# Mini_Black_Pill_grblHAL_v1.net
KiCad netlist of a schematic drawn in EAGLE
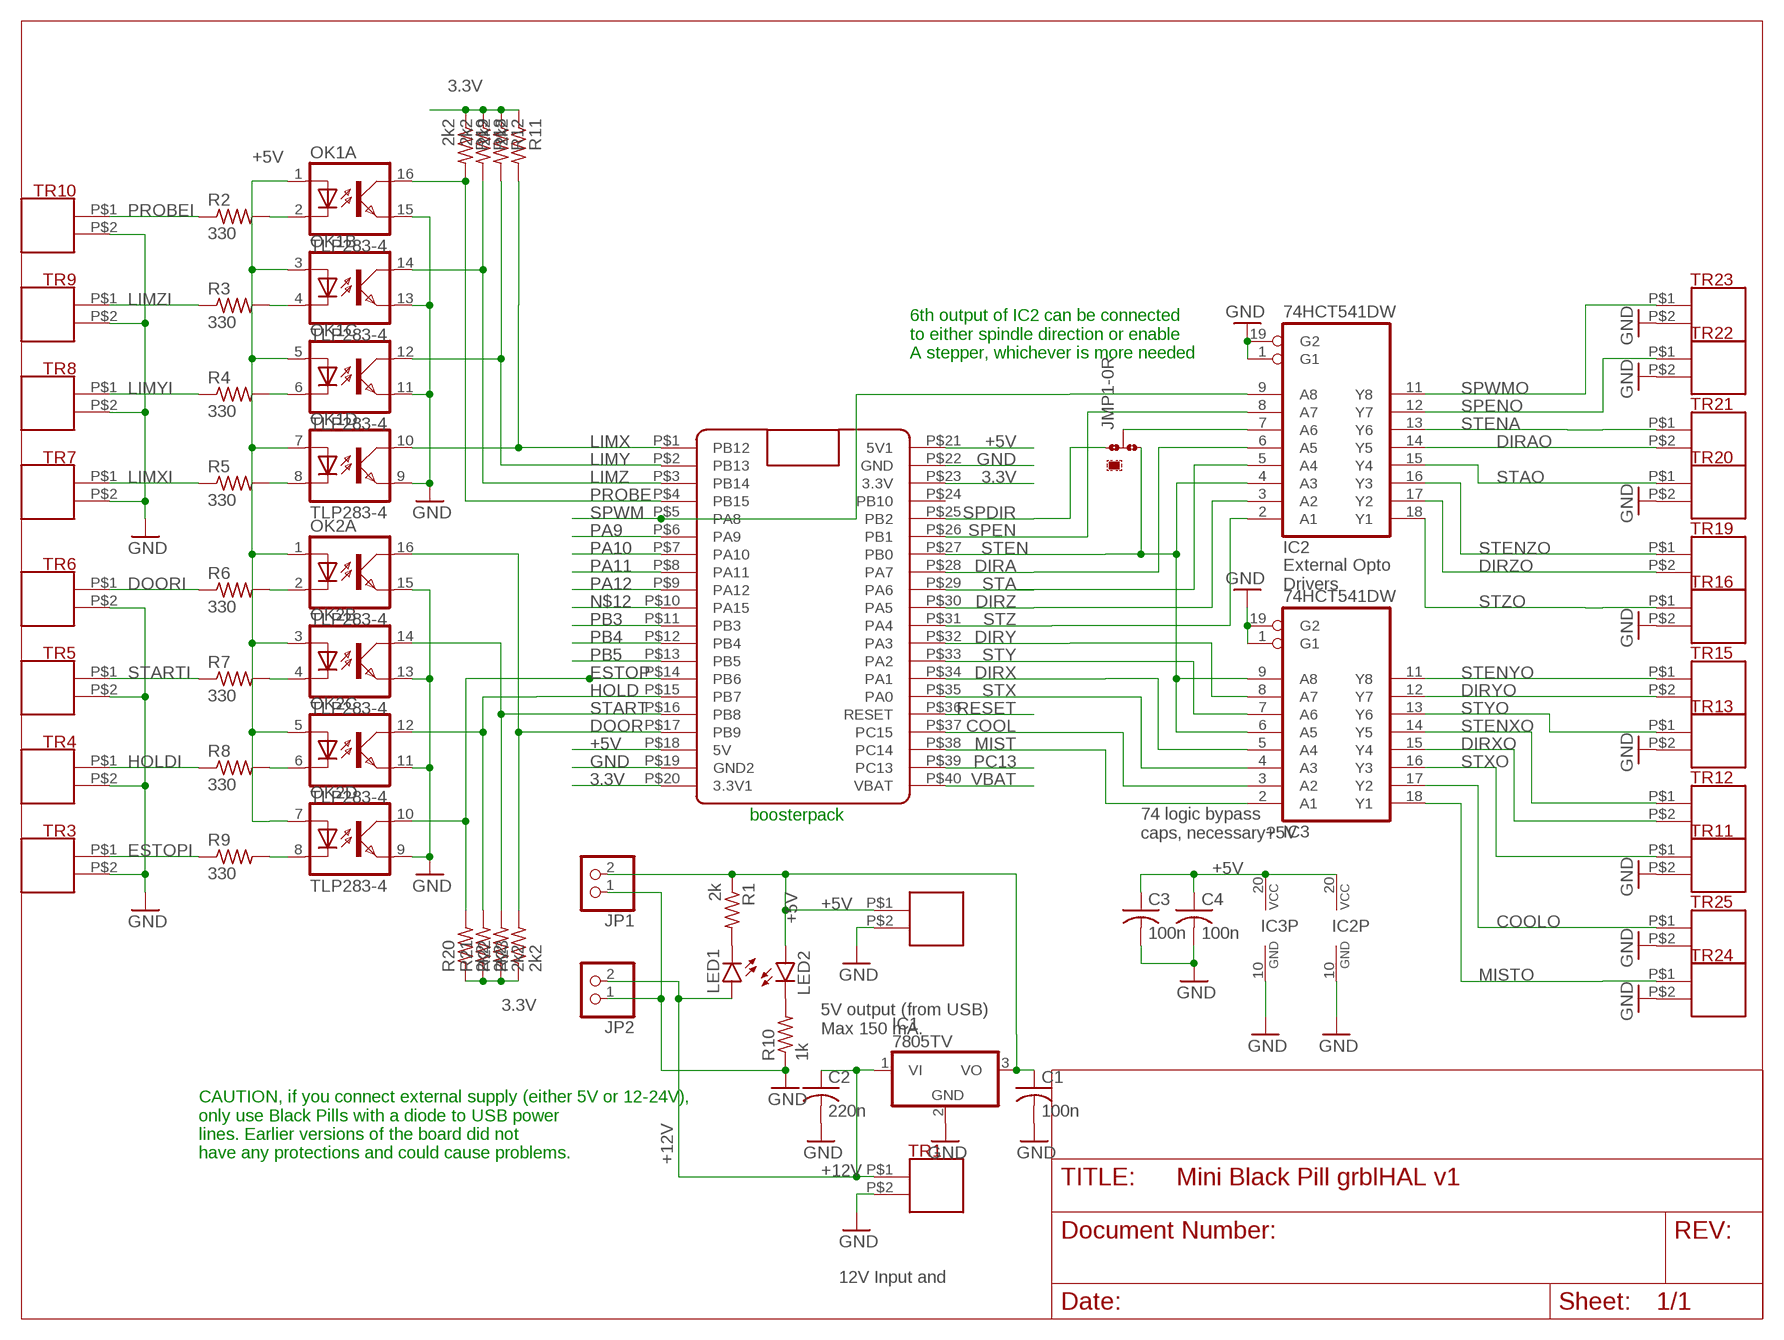
[diagram p0: schematic, sheet 1]

(export (version "E")
  (design (tool "Eeschema 10.0.6"))
  (components
    (comp (ref "C1")
      (value "100n")
      (footprint "eagle-import:C0805")
      (libsource (lib "eagle-import") (part "C-USC0805"))
    )
    (comp (ref "C2")
      (value "220n")
      (footprint "eagle-import:C0805")
      (libsource (lib "eagle-import") (part "C-USC0805"))
    )
    (comp (ref "C3")
      (value "100n")
      (footprint "eagle-import:C0805")
      (libsource (lib "eagle-import") (part "C-USC0805"))
    )
    (comp (ref "C4")
      (value "100n")
      (footprint "eagle-import:C0805")
      (libsource (lib "eagle-import") (part "C-USC0805"))
    )
    (comp (ref "IC1")
      (value "7805TV")
      (footprint "eagle-import:TO220V")
      (libsource (lib "eagle-import") (part "78TV05"))
    )
    (comp (ref "IC2")
      (value "74HCT541DW")
      (footprint "eagle-import:SO20W")
      (libsource (lib "eagle-import") (part "74541DWHCT"))
    )
    (comp (ref "IC3")
      (value "74HCT541DW")
      (footprint "eagle-import:SO20W")
      (libsource (lib "eagle-import") (part "74541DWHCT"))
    )
    (comp (ref "JMP1")
      (value "0R-JUMPA")
      (footprint "eagle-import:A0R-JMP")
      (libsource (lib "eagle-import") (part "0R-JUMPA"))
    )
    (comp (ref "JP1")
      (value "PINHD-1X2")
      (footprint "eagle-import:1X02")
      (libsource (lib "eagle-import") (part "PINHD-1X2"))
    )
    (comp (ref "JP2")
      (value "PINHD-1X2")
      (footprint "eagle-import:1X02")
      (libsource (lib "eagle-import") (part "PINHD-1X2"))
    )
    (comp (ref "LED1")
      (value "LED3MM")
      (footprint "eagle-import:LED3MM")
      (libsource (lib "eagle-import") (part "LED3MM"))
    )
    (comp (ref "LED2")
      (value "LED3MM")
      (footprint "eagle-import:LED3MM")
      (libsource (lib "eagle-import") (part "LED3MM"))
    )
    (comp (ref "OK1")
      (value "TLP283-4")
      (footprint "eagle-import:MINI-FLAT-16")
      (libsource (lib "eagle-import") (part "TLP283-4"))
    )
    (comp (ref "OK2")
      (value "TLP283-4")
      (footprint "eagle-import:MINI-FLAT-16")
      (libsource (lib "eagle-import") (part "TLP283-4"))
    )
    (comp (ref "R1")
      (value "2k")
      (footprint "eagle-import:R0805")
      (libsource (lib "eagle-import") (part "R-US_R0805"))
    )
    (comp (ref "R2")
      (value "330")
      (footprint "eagle-import:R0805")
      (libsource (lib "eagle-import") (part "R-US_R0805"))
    )
    (comp (ref "R3")
      (value "330")
      (footprint "eagle-import:R0805")
      (libsource (lib "eagle-import") (part "R-US_R0805"))
    )
    (comp (ref "R4")
      (value "330")
      (footprint "eagle-import:R0805")
      (libsource (lib "eagle-import") (part "R-US_R0805"))
    )
    (comp (ref "R5")
      (value "330")
      (footprint "eagle-import:R0805")
      (libsource (lib "eagle-import") (part "R-US_R0805"))
    )
    (comp (ref "R6")
      (value "330")
      (footprint "eagle-import:R0805")
      (libsource (lib "eagle-import") (part "R-US_R0805"))
    )
    (comp (ref "R7")
      (value "330")
      (footprint "eagle-import:R0805")
      (libsource (lib "eagle-import") (part "R-US_R0805"))
    )
    (comp (ref "R8")
      (value "330")
      (footprint "eagle-import:R0805")
      (libsource (lib "eagle-import") (part "R-US_R0805"))
    )
    (comp (ref "R9")
      (value "330")
      (footprint "eagle-import:R0805")
      (libsource (lib "eagle-import") (part "R-US_R0805"))
    )
    (comp (ref "R10")
      (value "1k")
      (footprint "eagle-import:R0805")
      (libsource (lib "eagle-import") (part "R-US_R0805"))
    )
    (comp (ref "R11")
      (value "2k2")
      (footprint "eagle-import:R0805")
      (libsource (lib "eagle-import") (part "R-US_R0805"))
    )
    (comp (ref "R12")
      (value "2k2")
      (footprint "eagle-import:R0805")
      (libsource (lib "eagle-import") (part "R-US_R0805"))
    )
    (comp (ref "R18")
      (value "2k2")
      (footprint "eagle-import:R0805")
      (libsource (lib "eagle-import") (part "R-US_R0805"))
    )
    (comp (ref "R19")
      (value "2k2")
      (footprint "eagle-import:R0805")
      (libsource (lib "eagle-import") (part "R-US_R0805"))
    )
    (comp (ref "R20")
      (value "2k2")
      (footprint "eagle-import:R0805")
      (libsource (lib "eagle-import") (part "R-US_R0805"))
    )
    (comp (ref "R21")
      (value "2k2")
      (footprint "eagle-import:R0805")
      (libsource (lib "eagle-import") (part "R-US_R0805"))
    )
    (comp (ref "R22")
      (value "2k2")
      (footprint "eagle-import:R0805")
      (libsource (lib "eagle-import") (part "R-US_R0805"))
    )
    (comp (ref "R23")
      (value "2k2")
      (footprint "eagle-import:R0805")
      (libsource (lib "eagle-import") (part "R-US_R0805"))
    )
    (comp (ref "TR1")
      (value "T35-2")
      (footprint "eagle-import:T35-2")
      (libsource (lib "eagle-import") (part "T35-2"))
    )
    (comp (ref "TR2")
      (value "T35-2")
      (footprint "eagle-import:T35-2")
      (libsource (lib "eagle-import") (part "T35-2"))
    )
    (comp (ref "TR3")
      (value "T35-2")
      (footprint "eagle-import:T35-2")
      (libsource (lib "eagle-import") (part "T35-2"))
    )
    (comp (ref "TR4")
      (value "T35-2")
      (footprint "eagle-import:T35-2")
      (libsource (lib "eagle-import") (part "T35-2"))
    )
    (comp (ref "TR5")
      (value "T35-2")
      (footprint "eagle-import:T35-2")
      (libsource (lib "eagle-import") (part "T35-2"))
    )
    (comp (ref "TR6")
      (value "T35-2")
      (footprint "eagle-import:T35-2")
      (libsource (lib "eagle-import") (part "T35-2"))
    )
    (comp (ref "TR7")
      (value "T35-2")
      (footprint "eagle-import:T35-2")
      (libsource (lib "eagle-import") (part "T35-2"))
    )
    (comp (ref "TR8")
      (value "T35-2")
      (footprint "eagle-import:T35-2")
      (libsource (lib "eagle-import") (part "T35-2"))
    )
    (comp (ref "TR9")
      (value "T35-2")
      (footprint "eagle-import:T35-2")
      (libsource (lib "eagle-import") (part "T35-2"))
    )
    (comp (ref "TR10")
      (value "T35-2")
      (footprint "eagle-import:T35-2")
      (libsource (lib "eagle-import") (part "T35-2"))
    )
    (comp (ref "TR11")
      (value "T35-2")
      (footprint "eagle-import:T35-2")
      (libsource (lib "eagle-import") (part "T35-2"))
    )
    (comp (ref "TR12")
      (value "T35-2")
      (footprint "eagle-import:T35-2")
      (libsource (lib "eagle-import") (part "T35-2"))
    )
    (comp (ref "TR13")
      (value "T35-2")
      (footprint "eagle-import:T35-2")
      (libsource (lib "eagle-import") (part "T35-2"))
    )
    (comp (ref "TR15")
      (value "T35-2")
      (footprint "eagle-import:T35-2")
      (libsource (lib "eagle-import") (part "T35-2"))
    )
    (comp (ref "TR16")
      (value "T35-2")
      (footprint "eagle-import:T35-2")
      (libsource (lib "eagle-import") (part "T35-2"))
    )
    (comp (ref "TR19")
      (value "T35-2")
      (footprint "eagle-import:T35-2")
      (libsource (lib "eagle-import") (part "T35-2"))
    )
    (comp (ref "TR20")
      (value "T35-2")
      (footprint "eagle-import:T35-2")
      (libsource (lib "eagle-import") (part "T35-2"))
    )
    (comp (ref "TR21")
      (value "T35-2")
      (footprint "eagle-import:T35-2")
      (libsource (lib "eagle-import") (part "T35-2"))
    )
    (comp (ref "TR22")
      (value "T35-2")
      (footprint "eagle-import:T35-2")
      (libsource (lib "eagle-import") (part "T35-2"))
    )
    (comp (ref "TR23")
      (value "T35-2")
      (footprint "eagle-import:T35-2")
      (libsource (lib "eagle-import") (part "T35-2"))
    )
    (comp (ref "TR24")
      (value "T35-2")
      (footprint "eagle-import:T35-2")
      (libsource (lib "eagle-import") (part "T35-2"))
    )
    (comp (ref "TR25")
      (value "T35-2")
      (footprint "eagle-import:T35-2")
      (libsource (lib "eagle-import") (part "T35-2"))
    )
    (comp (ref "U$2")
      (value "BLACK_PILL")
      (footprint "eagle-import:BLUE_PILL")
      (libsource (lib "eagle-import") (part "BLACK_PILL"))
    )
  )
  (nets
    (net (code "1") (name "/+5V") (class "Default")
      (node (ref "C1") (pin "1") (pinfunction "1_1") (pintype "passive"))
      (node (ref "C3") (pin "1") (pinfunction "1_1") (pintype "passive"))
      (node (ref "C4") (pin "1") (pinfunction "1_1") (pintype "passive"))
      (node (ref "IC1") (pin "3") (pinfunction "VO_3") (pintype "passive"))
      (node (ref "IC2") (pin "20") (pinfunction "VCC_20") (pintype "power_in"))
      (node (ref "IC3") (pin "20") (pinfunction "VCC_20") (pintype "power_in"))
      (node (ref "JP1") (pin "2") (pinfunction "2_2") (pintype "passive"))
      (node (ref "LED2") (pin "A") (pinfunction "A_A") (pintype "passive"))
      (node (ref "OK1") (pin "1") (pinfunction "A_1") (pintype "passive"))
      (node (ref "OK1") (pin "3") (pinfunction "A_3") (pintype "passive"))
      (node (ref "OK1") (pin "5") (pinfunction "A_5") (pintype "passive"))
      (node (ref "OK1") (pin "7") (pinfunction "A_7") (pintype "passive"))
      (node (ref "OK2") (pin "1") (pinfunction "A_1") (pintype "passive"))
      (node (ref "OK2") (pin "3") (pinfunction "A_3") (pintype "passive"))
      (node (ref "OK2") (pin "5") (pinfunction "A_5") (pintype "passive"))
      (node (ref "OK2") (pin "7") (pinfunction "A_7") (pintype "passive"))
      (node (ref "R1") (pin "1") (pinfunction "1_1") (pintype "passive"))
      (node (ref "TR2") (pin "P$1") (pinfunction "P$1_P$1") (pintype "bidirectional"))
      (node (ref "U$2") (pin "P$18") (pinfunction "5V_P$18") (pintype "bidirectional"))
      (node (ref "U$2") (pin "P$21") (pinfunction "5V1_P$21") (pintype "power_in"))
    )
    (net (code "2") (name "/+12V") (class "Default")
      (node (ref "C2") (pin "1") (pinfunction "1_1") (pintype "passive"))
      (node (ref "IC1") (pin "1") (pinfunction "VI_1") (pintype "input"))
      (node (ref "JP2") (pin "2") (pinfunction "2_2") (pintype "passive"))
      (node (ref "LED1") (pin "A") (pinfunction "A_A") (pintype "passive"))
      (node (ref "TR1") (pin "P$1") (pinfunction "P$1_P$1") (pintype "bidirectional"))
    )
    (net (code "3") (name "/3.3V") (class "Default")
      (node (ref "R11") (pin "1") (pinfunction "1_1") (pintype "passive"))
      (node (ref "R12") (pin "1") (pinfunction "1_1") (pintype "passive"))
      (node (ref "R18") (pin "1") (pinfunction "1_1") (pintype "passive"))
      (node (ref "R19") (pin "1") (pinfunction "1_1") (pintype "passive"))
      (node (ref "R20") (pin "1") (pinfunction "1_1") (pintype "passive"))
      (node (ref "R21") (pin "1") (pinfunction "1_1") (pintype "passive"))
      (node (ref "R22") (pin "1") (pinfunction "1_1") (pintype "passive"))
      (node (ref "R23") (pin "1") (pinfunction "1_1") (pintype "passive"))
      (node (ref "U$2") (pin "P$20") (pinfunction "3.3V1_P$20") (pintype "bidirectional"))
      (node (ref "U$2") (pin "P$23") (pinfunction "3.3V_P$23") (pintype "bidirectional"))
    )
    (net (code "4") (name "/COOL") (class "Default")
      (node (ref "IC3") (pin "3") (pinfunction "A2_3") (pintype "input"))
      (node (ref "U$2") (pin "P$37") (pinfunction "PC15_P$37") (pintype "bidirectional"))
    )
    (net (code "5") (name "/COOLO") (class "Default")
      (node (ref "IC3") (pin "17") (pinfunction "Y2_17") (pintype "tri_state"))
      (node (ref "TR25") (pin "P$1") (pinfunction "P$1_P$1") (pintype "bidirectional"))
    )
    (net (code "6") (name "/DIRA") (class "Default")
      (node (ref "IC2") (pin "6") (pinfunction "A5_6") (pintype "input"))
      (node (ref "U$2") (pin "P$28") (pinfunction "PA7_P$28") (pintype "bidirectional"))
    )
    (net (code "7") (name "/DIRAO") (class "Default")
      (node (ref "IC2") (pin "14") (pinfunction "Y5_14") (pintype "tri_state"))
      (node (ref "TR21") (pin "P$2") (pinfunction "P$2_P$2") (pintype "bidirectional"))
    )
    (net (code "8") (name "/DIRX") (class "Default")
      (node (ref "IC3") (pin "5") (pinfunction "A4_5") (pintype "input"))
      (node (ref "U$2") (pin "P$34") (pinfunction "PA1_P$34") (pintype "bidirectional"))
    )
    (net (code "9") (name "/DIRXO") (class "Default")
      (node (ref "IC3") (pin "15") (pinfunction "Y4_15") (pintype "tri_state"))
      (node (ref "TR12") (pin "P$2") (pinfunction "P$2_P$2") (pintype "bidirectional"))
    )
    (net (code "10") (name "/DIRY") (class "Default")
      (node (ref "IC3") (pin "8") (pinfunction "A7_8") (pintype "input"))
      (node (ref "U$2") (pin "P$32") (pinfunction "PA3_P$32") (pintype "bidirectional"))
    )
    (net (code "11") (name "/DIRYO") (class "Default")
      (node (ref "IC3") (pin "12") (pinfunction "Y7_12") (pintype "tri_state"))
      (node (ref "TR15") (pin "P$2") (pinfunction "P$2_P$2") (pintype "bidirectional"))
    )
    (net (code "12") (name "/DIRZ") (class "Default")
      (node (ref "IC2") (pin "3") (pinfunction "A2_3") (pintype "input"))
      (node (ref "U$2") (pin "P$30") (pinfunction "PA5_P$30") (pintype "bidirectional"))
    )
    (net (code "13") (name "/DIRZO") (class "Default")
      (node (ref "IC2") (pin "17") (pinfunction "Y2_17") (pintype "tri_state"))
      (node (ref "TR19") (pin "P$2") (pinfunction "P$2_P$2") (pintype "bidirectional"))
    )
    (net (code "14") (name "/DOOR") (class "Default")
      (node (ref "OK2") (pin "16") (pinfunction "COL_16") (pintype "passive"))
      (node (ref "R23") (pin "2") (pinfunction "2_2") (pintype "passive"))
      (node (ref "U$2") (pin "P$17") (pinfunction "PB9_P$17") (pintype "bidirectional"))
    )
    (net (code "15") (name "/DOORI") (class "Default")
      (node (ref "R6") (pin "1") (pinfunction "1_1") (pintype "passive"))
      (node (ref "TR6") (pin "P$1") (pinfunction "P$1_P$1") (pintype "bidirectional"))
    )
    (net (code "16") (name "/ESTOP") (class "Default")
      (node (ref "OK2") (pin "10") (pinfunction "COL_10") (pintype "passive"))
      (node (ref "R20") (pin "2") (pinfunction "2_2") (pintype "passive"))
      (node (ref "U$2") (pin "P$14") (pinfunction "PB6_P$14") (pintype "bidirectional"))
    )
    (net (code "17") (name "/ESTOPI") (class "Default")
      (node (ref "R9") (pin "1") (pinfunction "1_1") (pintype "passive"))
      (node (ref "TR3") (pin "P$1") (pinfunction "P$1_P$1") (pintype "bidirectional"))
    )
    (net (code "18") (name "/HOLD") (class "Default")
      (node (ref "OK2") (pin "12") (pinfunction "COL_12") (pintype "passive"))
      (node (ref "R21") (pin "2") (pinfunction "2_2") (pintype "passive"))
      (node (ref "U$2") (pin "P$15") (pinfunction "PB7_P$15") (pintype "bidirectional"))
    )
    (net (code "19") (name "/HOLDI") (class "Default")
      (node (ref "R8") (pin "1") (pinfunction "1_1") (pintype "passive"))
      (node (ref "TR4") (pin "P$1") (pinfunction "P$1_P$1") (pintype "bidirectional"))
    )
    (net (code "20") (name "/LIMX") (class "Default")
      (node (ref "OK1") (pin "10") (pinfunction "COL_10") (pintype "passive"))
      (node (ref "R11") (pin "2") (pinfunction "2_2") (pintype "passive"))
      (node (ref "U$2") (pin "P$1") (pinfunction "PB12_P$1") (pintype "bidirectional"))
    )
    (net (code "21") (name "/LIMXI") (class "Default")
      (node (ref "R5") (pin "1") (pinfunction "1_1") (pintype "passive"))
      (node (ref "TR7") (pin "P$1") (pinfunction "P$1_P$1") (pintype "bidirectional"))
    )
    (net (code "22") (name "/LIMY") (class "Default")
      (node (ref "OK1") (pin "12") (pinfunction "COL_12") (pintype "passive"))
      (node (ref "R12") (pin "2") (pinfunction "2_2") (pintype "passive"))
      (node (ref "U$2") (pin "P$2") (pinfunction "PB13_P$2") (pintype "bidirectional"))
    )
    (net (code "23") (name "/LIMYI") (class "Default")
      (node (ref "R4") (pin "1") (pinfunction "1_1") (pintype "passive"))
      (node (ref "TR8") (pin "P$1") (pinfunction "P$1_P$1") (pintype "bidirectional"))
    )
    (net (code "24") (name "/LIMZ") (class "Default")
      (node (ref "OK1") (pin "14") (pinfunction "COL_14") (pintype "passive"))
      (node (ref "R18") (pin "2") (pinfunction "2_2") (pintype "passive"))
      (node (ref "U$2") (pin "P$3") (pinfunction "PB14_P$3") (pintype "bidirectional"))
    )
    (net (code "25") (name "/LIMZI") (class "Default")
      (node (ref "R3") (pin "1") (pinfunction "1_1") (pintype "passive"))
      (node (ref "TR9") (pin "P$1") (pinfunction "P$1_P$1") (pintype "bidirectional"))
    )
    (net (code "26") (name "/MIST") (class "Default")
      (node (ref "IC3") (pin "2") (pinfunction "A1_2") (pintype "input"))
      (node (ref "U$2") (pin "P$38") (pinfunction "PC14_P$38") (pintype "bidirectional"))
    )
    (net (code "27") (name "/MISTO") (class "Default")
      (node (ref "IC3") (pin "18") (pinfunction "Y1_18") (pintype "tri_state"))
      (node (ref "TR24") (pin "P$1") (pinfunction "P$1_P$1") (pintype "bidirectional"))
    )
    (net (code "28") (name "/N$12") (class "Default")
      (node (ref "U$2") (pin "P$10") (pinfunction "PA15_P$10") (pintype "bidirectional"))
    )
    (net (code "29") (name "/PA9") (class "Default")
      (node (ref "U$2") (pin "P$6") (pinfunction "PA9_P$6") (pintype "bidirectional"))
    )
    (net (code "30") (name "/PA10") (class "Default")
      (node (ref "U$2") (pin "P$7") (pinfunction "PA10_P$7") (pintype "bidirectional"))
    )
    (net (code "31") (name "/PA11") (class "Default")
      (node (ref "U$2") (pin "P$8") (pinfunction "PA11_P$8") (pintype "bidirectional"))
    )
    (net (code "32") (name "/PA12") (class "Default")
      (node (ref "U$2") (pin "P$9") (pinfunction "PA12_P$9") (pintype "bidirectional"))
    )
    (net (code "33") (name "/PB3") (class "Default")
      (node (ref "U$2") (pin "P$11") (pinfunction "PB3_P$11") (pintype "bidirectional"))
    )
    (net (code "34") (name "/PB4") (class "Default")
      (node (ref "U$2") (pin "P$12") (pinfunction "PB4_P$12") (pintype "bidirectional"))
    )
    (net (code "35") (name "/PB5") (class "Default")
      (node (ref "U$2") (pin "P$13") (pinfunction "PB5_P$13") (pintype "bidirectional"))
    )
    (net (code "36") (name "/PC13") (class "Default")
      (node (ref "U$2") (pin "P$39") (pinfunction "PC13_P$39") (pintype "bidirectional"))
    )
    (net (code "37") (name "/PROBE") (class "Default")
      (node (ref "OK1") (pin "16") (pinfunction "COL_16") (pintype "passive"))
      (node (ref "R19") (pin "2") (pinfunction "2_2") (pintype "passive"))
      (node (ref "U$2") (pin "P$4") (pinfunction "PB15_P$4") (pintype "bidirectional"))
    )
    (net (code "38") (name "/PROBEI") (class "Default")
      (node (ref "R2") (pin "1") (pinfunction "1_1") (pintype "passive"))
      (node (ref "TR10") (pin "P$1") (pinfunction "P$1_P$1") (pintype "bidirectional"))
    )
    (net (code "39") (name "/RESET") (class "Default")
      (node (ref "U$2") (pin "P$36") (pinfunction "RESET_P$36") (pintype "bidirectional"))
    )
    (net (code "40") (name "/SPDIR") (class "Default")
      (node (ref "JMP1") (pin "1") (pinfunction "1_1") (pintype "passive"))
      (node (ref "U$2") (pin "P$25") (pinfunction "PB2_P$25") (pintype "bidirectional"))
    )
    (net (code "41") (name "/SPEN") (class "Default")
      (node (ref "IC2") (pin "8") (pinfunction "A7_8") (pintype "input"))
      (node (ref "U$2") (pin "P$26") (pinfunction "PB1_P$26") (pintype "bidirectional"))
    )
    (net (code "42") (name "/SPENO") (class "Default")
      (node (ref "IC2") (pin "12") (pinfunction "Y7_12") (pintype "tri_state"))
      (node (ref "TR22") (pin "P$1") (pinfunction "P$1_P$1") (pintype "bidirectional"))
    )
    (net (code "43") (name "/SPWM") (class "Default")
      (node (ref "IC2") (pin "9") (pinfunction "A8_9") (pintype "input"))
      (node (ref "U$2") (pin "P$5") (pinfunction "PA8_P$5") (pintype "bidirectional"))
    )
    (net (code "44") (name "/SPWMO") (class "Default")
      (node (ref "IC2") (pin "11") (pinfunction "Y8_11") (pintype "tri_state"))
      (node (ref "TR23") (pin "P$1") (pinfunction "P$1_P$1") (pintype "bidirectional"))
    )
    (net (code "45") (name "/STA") (class "Default")
      (node (ref "IC2") (pin "5") (pinfunction "A4_5") (pintype "input"))
      (node (ref "U$2") (pin "P$29") (pinfunction "PA6_P$29") (pintype "bidirectional"))
    )
    (net (code "46") (name "/STAO") (class "Default")
      (node (ref "IC2") (pin "15") (pinfunction "Y4_15") (pintype "tri_state"))
      (node (ref "TR20") (pin "P$1") (pinfunction "P$1_P$1") (pintype "bidirectional"))
    )
    (net (code "47") (name "/START") (class "Default")
      (node (ref "OK2") (pin "14") (pinfunction "COL_14") (pintype "passive"))
      (node (ref "R22") (pin "2") (pinfunction "2_2") (pintype "passive"))
      (node (ref "U$2") (pin "P$16") (pinfunction "PB8_P$16") (pintype "bidirectional"))
    )
    (net (code "48") (name "/STARTI") (class "Default")
      (node (ref "R7") (pin "1") (pinfunction "1_1") (pintype "passive"))
      (node (ref "TR5") (pin "P$1") (pinfunction "P$1_P$1") (pintype "bidirectional"))
    )
    (net (code "49") (name "/STEN") (class "Default")
      (node (ref "IC2") (pin "4") (pinfunction "A3_4") (pintype "input"))
      (node (ref "IC3") (pin "6") (pinfunction "A5_6") (pintype "input"))
      (node (ref "IC3") (pin "9") (pinfunction "A8_9") (pintype "input"))
      (node (ref "JMP1") (pin "3") (pinfunction "3_3") (pintype "passive"))
      (node (ref "U$2") (pin "P$27") (pinfunction "PB0_P$27") (pintype "bidirectional"))
    )
    (net (code "50") (name "/STENA") (class "Default")
      (node (ref "IC2") (pin "13") (pinfunction "Y6_13") (pintype "tri_state"))
      (node (ref "TR21") (pin "P$1") (pinfunction "P$1_P$1") (pintype "bidirectional"))
    )
    (net (code "51") (name "/STENXO") (class "Default")
      (node (ref "IC3") (pin "14") (pinfunction "Y5_14") (pintype "tri_state"))
      (node (ref "TR12") (pin "P$1") (pinfunction "P$1_P$1") (pintype "bidirectional"))
    )
    (net (code "52") (name "/STENYO") (class "Default")
      (node (ref "IC3") (pin "11") (pinfunction "Y8_11") (pintype "tri_state"))
      (node (ref "TR15") (pin "P$1") (pinfunction "P$1_P$1") (pintype "bidirectional"))
    )
    (net (code "53") (name "/STENZO") (class "Default")
      (node (ref "IC2") (pin "16") (pinfunction "Y3_16") (pintype "tri_state"))
      (node (ref "TR19") (pin "P$1") (pinfunction "P$1_P$1") (pintype "bidirectional"))
    )
    (net (code "54") (name "/STX") (class "Default")
      (node (ref "IC3") (pin "4") (pinfunction "A3_4") (pintype "input"))
      (node (ref "U$2") (pin "P$35") (pinfunction "PA0_P$35") (pintype "bidirectional"))
    )
    (net (code "55") (name "/STXO") (class "Default")
      (node (ref "IC3") (pin "16") (pinfunction "Y3_16") (pintype "tri_state"))
      (node (ref "TR11") (pin "P$1") (pinfunction "P$1_P$1") (pintype "bidirectional"))
    )
    (net (code "56") (name "/STY") (class "Default")
      (node (ref "IC3") (pin "7") (pinfunction "A6_7") (pintype "input"))
      (node (ref "U$2") (pin "P$33") (pinfunction "PA2_P$33") (pintype "bidirectional"))
    )
    (net (code "57") (name "/STYO") (class "Default")
      (node (ref "IC3") (pin "13") (pinfunction "Y6_13") (pintype "tri_state"))
      (node (ref "TR13") (pin "P$1") (pinfunction "P$1_P$1") (pintype "bidirectional"))
    )
    (net (code "58") (name "/STZ") (class "Default")
      (node (ref "IC2") (pin "2") (pinfunction "A1_2") (pintype "input"))
      (node (ref "U$2") (pin "P$31") (pinfunction "PA4_P$31") (pintype "bidirectional"))
    )
    (net (code "59") (name "/STZO") (class "Default")
      (node (ref "IC2") (pin "18") (pinfunction "Y1_18") (pintype "tri_state"))
      (node (ref "TR16") (pin "P$1") (pinfunction "P$1_P$1") (pintype "bidirectional"))
    )
    (net (code "60") (name "/VBAT") (class "Default")
      (node (ref "U$2") (pin "P$40") (pinfunction "VBAT_P$40") (pintype "bidirectional"))
    )
    (net (code "61") (name "GND") (class "Default")
      (node (ref "C1") (pin "2") (pinfunction "2_2") (pintype "passive"))
      (node (ref "C2") (pin "2") (pinfunction "2_2") (pintype "passive"))
      (node (ref "C3") (pin "2") (pinfunction "2_2") (pintype "passive"))
      (node (ref "C4") (pin "2") (pinfunction "2_2") (pintype "passive"))
      (node (ref "IC1") (pin "2") (pinfunction "GND_2") (pintype "passive"))
      (node (ref "IC2") (pin "1") (pinfunction "G1_1") (pintype "input"))
      (node (ref "IC2") (pin "10") (pinfunction "GND_10") (pintype "power_in"))
      (node (ref "IC2") (pin "19") (pinfunction "G2_19") (pintype "input"))
      (node (ref "IC3") (pin "1") (pinfunction "G1_1") (pintype "input"))
      (node (ref "IC3") (pin "10") (pinfunction "GND_10") (pintype "power_in"))
      (node (ref "IC3") (pin "19") (pinfunction "G2_19") (pintype "input"))
      (node (ref "JP1") (pin "1") (pinfunction "1_1") (pintype "passive"))
      (node (ref "JP2") (pin "1") (pinfunction "1_1") (pintype "passive"))
      (node (ref "OK1") (pin "11") (pinfunction "EMIT_11") (pintype "passive"))
      (node (ref "OK1") (pin "13") (pinfunction "EMIT_13") (pintype "passive"))
      (node (ref "OK1") (pin "15") (pinfunction "EMIT_15") (pintype "passive"))
      (node (ref "OK1") (pin "9") (pinfunction "EMIT_9") (pintype "passive"))
      (node (ref "OK2") (pin "11") (pinfunction "EMIT_11") (pintype "passive"))
      (node (ref "OK2") (pin "13") (pinfunction "EMIT_13") (pintype "passive"))
      (node (ref "OK2") (pin "15") (pinfunction "EMIT_15") (pintype "passive"))
      (node (ref "OK2") (pin "9") (pinfunction "EMIT_9") (pintype "passive"))
      (node (ref "R10") (pin "1") (pinfunction "1_1") (pintype "passive"))
      (node (ref "TR1") (pin "P$2") (pinfunction "P$2_P$2") (pintype "bidirectional"))
      (node (ref "TR10") (pin "P$2") (pinfunction "P$2_P$2") (pintype "bidirectional"))
      (node (ref "TR11") (pin "P$2") (pinfunction "P$2_P$2") (pintype "bidirectional"))
      (node (ref "TR13") (pin "P$2") (pinfunction "P$2_P$2") (pintype "bidirectional"))
      (node (ref "TR16") (pin "P$2") (pinfunction "P$2_P$2") (pintype "bidirectional"))
      (node (ref "TR2") (pin "P$2") (pinfunction "P$2_P$2") (pintype "bidirectional"))
      (node (ref "TR20") (pin "P$2") (pinfunction "P$2_P$2") (pintype "bidirectional"))
      (node (ref "TR22") (pin "P$2") (pinfunction "P$2_P$2") (pintype "bidirectional"))
      (node (ref "TR23") (pin "P$2") (pinfunction "P$2_P$2") (pintype "bidirectional"))
      (node (ref "TR24") (pin "P$2") (pinfunction "P$2_P$2") (pintype "bidirectional"))
      (node (ref "TR25") (pin "P$2") (pinfunction "P$2_P$2") (pintype "bidirectional"))
      (node (ref "TR3") (pin "P$2") (pinfunction "P$2_P$2") (pintype "bidirectional"))
      (node (ref "TR4") (pin "P$2") (pinfunction "P$2_P$2") (pintype "bidirectional"))
      (node (ref "TR5") (pin "P$2") (pinfunction "P$2_P$2") (pintype "bidirectional"))
      (node (ref "TR6") (pin "P$2") (pinfunction "P$2_P$2") (pintype "bidirectional"))
      (node (ref "TR7") (pin "P$2") (pinfunction "P$2_P$2") (pintype "bidirectional"))
      (node (ref "TR8") (pin "P$2") (pinfunction "P$2_P$2") (pintype "bidirectional"))
      (node (ref "TR9") (pin "P$2") (pinfunction "P$2_P$2") (pintype "bidirectional"))
      (node (ref "U$2") (pin "P$19") (pinfunction "GND2_P$19") (pintype "bidirectional"))
      (node (ref "U$2") (pin "P$22") (pinfunction "GND_P$22") (pintype "bidirectional"))
    )
    (net (code "62") (name "Net-(IC2A-A6)") (class "Default")
      (node (ref "IC2") (pin "7") (pinfunction "A6_7") (pintype "input"))
      (node (ref "JMP1") (pin "2") (pinfunction "2_2") (pintype "passive"))
    )
    (net (code "63") (name "Net-(LED1-C)") (class "Default")
      (node (ref "LED1") (pin "K") (pinfunction "C_K") (pintype "passive"))
      (node (ref "R1") (pin "2") (pinfunction "2_2") (pintype "passive"))
    )
    (net (code "64") (name "Net-(LED2-C)") (class "Default")
      (node (ref "LED2") (pin "K") (pinfunction "C_K") (pintype "passive"))
      (node (ref "R10") (pin "2") (pinfunction "2_2") (pintype "passive"))
    )
    (net (code "65") (name "Net-(OK1A-C)") (class "Default")
      (node (ref "OK1") (pin "2") (pinfunction "C_2") (pintype "passive"))
      (node (ref "R2") (pin "2") (pinfunction "2_2") (pintype "passive"))
    )
    (net (code "66") (name "Net-(OK1B-C)") (class "Default")
      (node (ref "OK1") (pin "4") (pinfunction "C_4") (pintype "passive"))
      (node (ref "R3") (pin "2") (pinfunction "2_2") (pintype "passive"))
    )
    (net (code "67") (name "Net-(OK1C-C)") (class "Default")
      (node (ref "OK1") (pin "6") (pinfunction "C_6") (pintype "passive"))
      (node (ref "R4") (pin "2") (pinfunction "2_2") (pintype "passive"))
    )
    (net (code "68") (name "Net-(OK1D-C)") (class "Default")
      (node (ref "OK1") (pin "8") (pinfunction "C_8") (pintype "passive"))
      (node (ref "R5") (pin "2") (pinfunction "2_2") (pintype "passive"))
    )
    (net (code "69") (name "Net-(OK2A-C)") (class "Default")
      (node (ref "OK2") (pin "2") (pinfunction "C_2") (pintype "passive"))
      (node (ref "R6") (pin "2") (pinfunction "2_2") (pintype "passive"))
    )
    (net (code "70") (name "Net-(OK2B-C)") (class "Default")
      (node (ref "OK2") (pin "4") (pinfunction "C_4") (pintype "passive"))
      (node (ref "R7") (pin "2") (pinfunction "2_2") (pintype "passive"))
    )
    (net (code "71") (name "Net-(OK2C-C)") (class "Default")
      (node (ref "OK2") (pin "6") (pinfunction "C_6") (pintype "passive"))
      (node (ref "R8") (pin "2") (pinfunction "2_2") (pintype "passive"))
    )
    (net (code "72") (name "Net-(OK2D-C)") (class "Default")
      (node (ref "OK2") (pin "8") (pinfunction "C_8") (pintype "passive"))
      (node (ref "R9") (pin "2") (pinfunction "2_2") (pintype "passive"))
    )
    (net (code "73") (name "unconnected-(U$2-PB10-PadP$24)") (class "Default")
      (node (ref "U$2") (pin "P$24") (pinfunction "PB10_P$24") (pintype "bidirectional"))
    )
  )
)
